# BluetoothB1.net
KiCad netlist of a schematic drawn in EAGLE
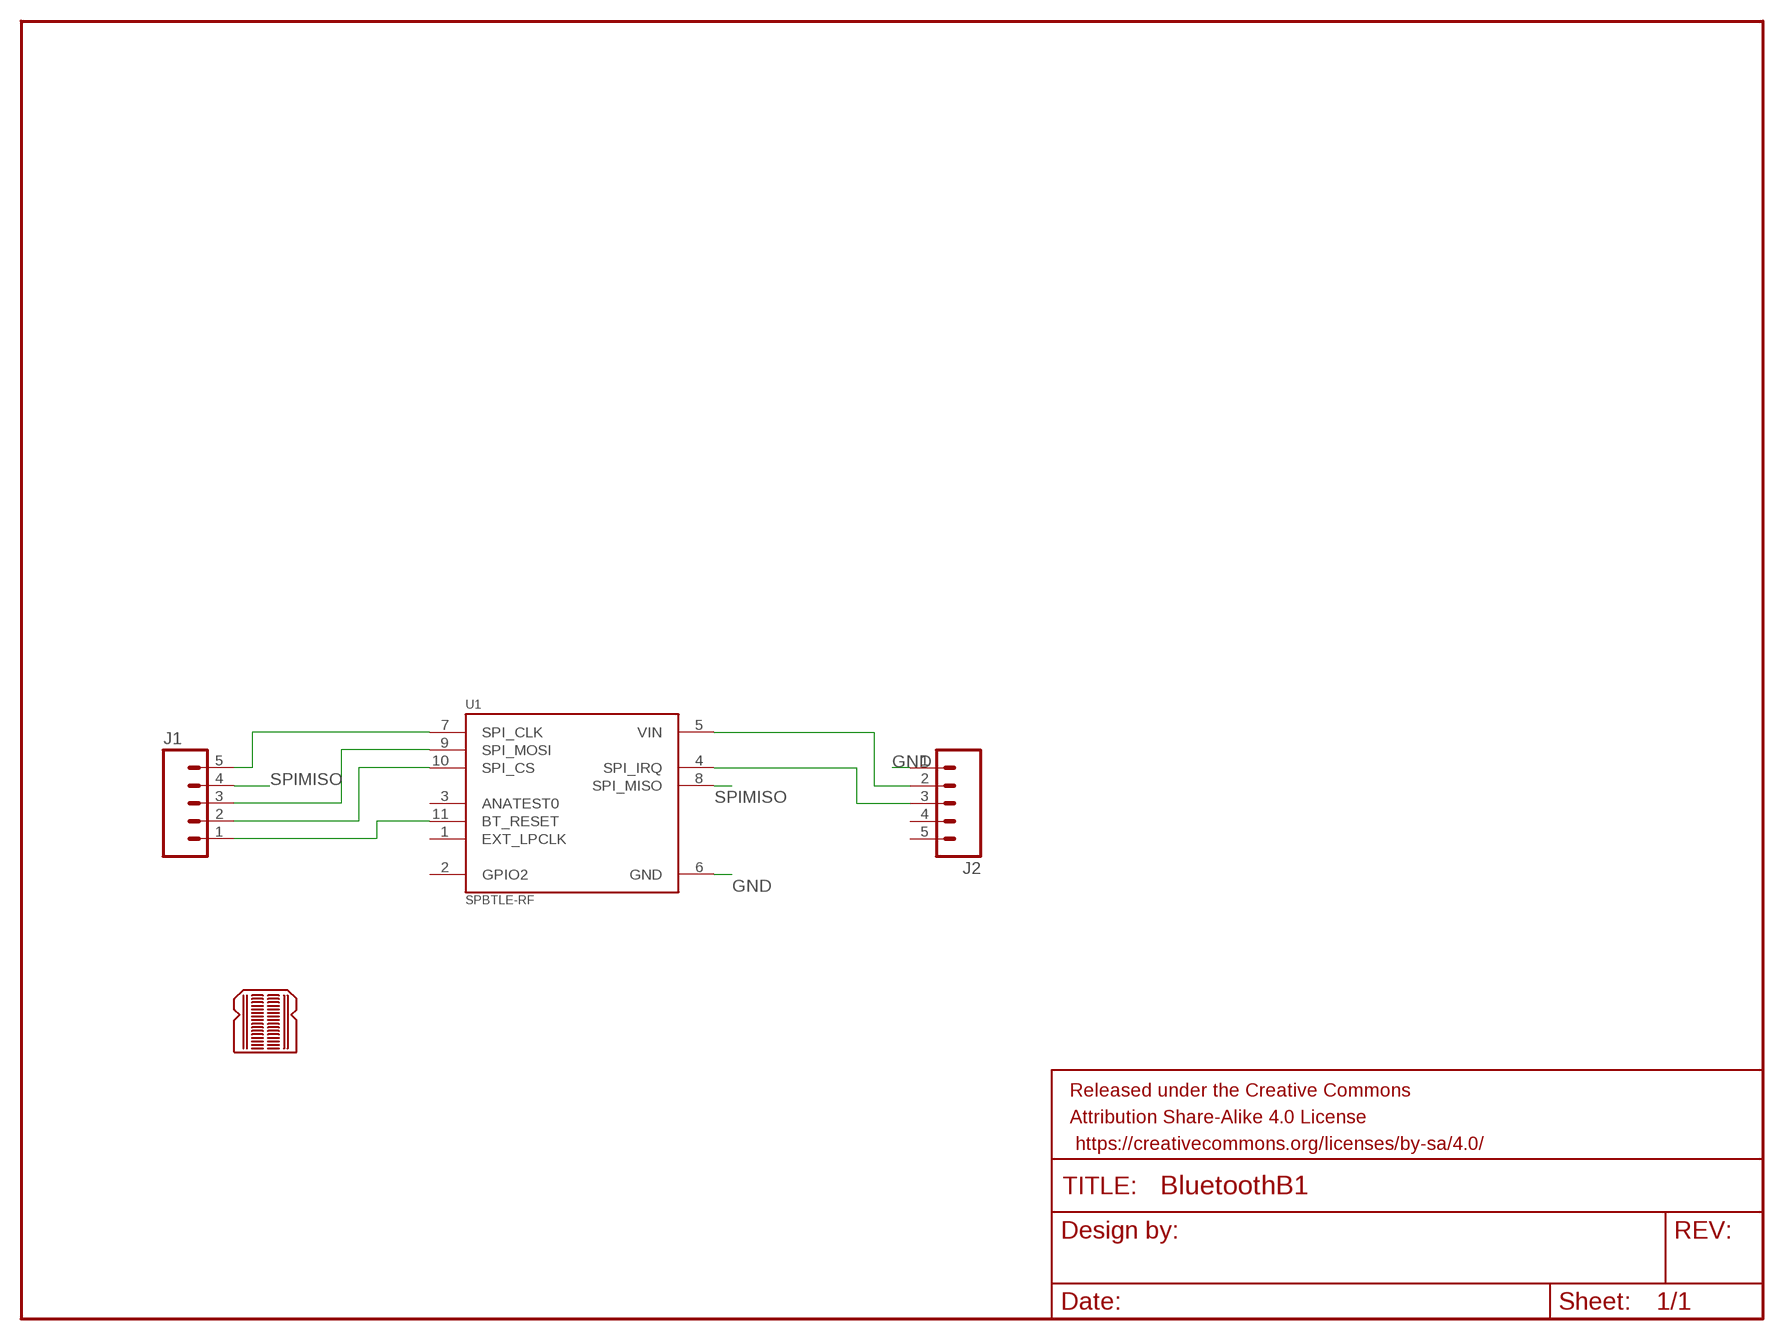
[diagram p0: schematic, sheet 1]

(export (version "E")
  (design (tool "Eeschema 10.0.6"))
  (components
    (comp (ref "FRAME1")
      (value "FRAME-LETTER")
      (footprint "eagle-import:CREATIVE_COMMONS")
      (libsource (lib "eagle-import") (part "FRAME-LETTER"))
    )
    (comp (ref "J1")
      (value "M05PTH")
      (footprint "eagle-import:1X05")
      (libsource (lib "eagle-import") (part "M05PTH"))
    )
    (comp (ref "J2")
      (value "M05PTH")
      (footprint "eagle-import:1X05")
      (libsource (lib "eagle-import") (part "M05PTH"))
    )
    (comp (ref "LOGO1")
      (value "BREADBOARD_PATTERN")
      (footprint "eagle-import:BREADBOARD_SPACING")
      (libsource (lib "eagle-import") (part "BREADBOARD_PATTERN"))
    )
    (comp (ref "U1")
      (value "SPBTLE-RF")
      (footprint "eagle-import:XCVR_SPBTLE-RF")
      (fields (field (name "MF") "STMicroelectronics"))
      (libsource (lib "eagle-import") (part "SPBTLE-RF"))
    )
  )
  (nets
    (net (code "1") (name "/GND") (class "Default")
      (node (ref "J2") (pin "1") (pinfunction "1_1") (pintype "passive"))
      (node (ref "U1") (pin "6") (pinfunction "GND_6") (pintype "power_in"))
    )
    (net (code "2") (name "/SPIMISO") (class "Default")
      (node (ref "J1") (pin "4") (pinfunction "4_4") (pintype "passive"))
      (node (ref "U1") (pin "8") (pinfunction "SPI_MISO_8") (pintype "output"))
    )
    (net (code "3") (name "Net-(U1-BT_RESET)") (class "Default")
      (node (ref "J1") (pin "1") (pinfunction "1_1") (pintype "passive"))
      (node (ref "U1") (pin "11") (pinfunction "BT_RESET_11") (pintype "input"))
    )
    (net (code "4") (name "Net-(U1-SPI_CLK)") (class "Default")
      (node (ref "J1") (pin "5") (pinfunction "5_5") (pintype "passive"))
      (node (ref "U1") (pin "7") (pinfunction "SPI_CLK_7") (pintype "input"))
    )
    (net (code "5") (name "Net-(U1-SPI_CS)") (class "Default")
      (node (ref "J1") (pin "2") (pinfunction "2_2") (pintype "passive"))
      (node (ref "U1") (pin "10") (pinfunction "SPI_CS_10") (pintype "input"))
    )
    (net (code "6") (name "Net-(U1-SPI_IRQ)") (class "Default")
      (node (ref "J2") (pin "3") (pinfunction "3_3") (pintype "passive"))
      (node (ref "U1") (pin "4") (pinfunction "SPI_IRQ_4") (pintype "output"))
    )
    (net (code "7") (name "Net-(U1-SPI_MOSI)") (class "Default")
      (node (ref "J1") (pin "3") (pinfunction "3_3") (pintype "passive"))
      (node (ref "U1") (pin "9") (pinfunction "SPI_MOSI_9") (pintype "input"))
    )
    (net (code "8") (name "Net-(U1-VIN)") (class "Default")
      (node (ref "J2") (pin "2") (pinfunction "2_2") (pintype "passive"))
      (node (ref "U1") (pin "5") (pinfunction "VIN_5") (pintype "power_in"))
    )
    (net (code "9") (name "unconnected-(J2-Pad4)") (class "Default")
      (node (ref "J2") (pin "4") (pinfunction "4_4") (pintype "passive"))
    )
    (net (code "10") (name "unconnected-(J2-Pad5)") (class "Default")
      (node (ref "J2") (pin "5") (pinfunction "5_5") (pintype "passive"))
    )
    (net (code "11") (name "unconnected-(U1-ANATEST0-Pad3)") (class "Default")
      (node (ref "U1") (pin "3") (pinfunction "ANATEST0_3") (pintype "input"))
    )
    (net (code "12") (name "unconnected-(U1-EXT_LPCLK-Pad1)") (class "Default")
      (node (ref "U1") (pin "1") (pinfunction "EXT_LPCLK_1") (pintype "input"))
    )
    (net (code "13") (name "unconnected-(U1-GPIO2-Pad2)") (class "Default")
      (node (ref "U1") (pin "2") (pinfunction "GPIO2_2") (pintype "bidirectional"))
    )
  )
)
